# AMP_1_0.net
KiCad netlist of a schematic drawn in EAGLE
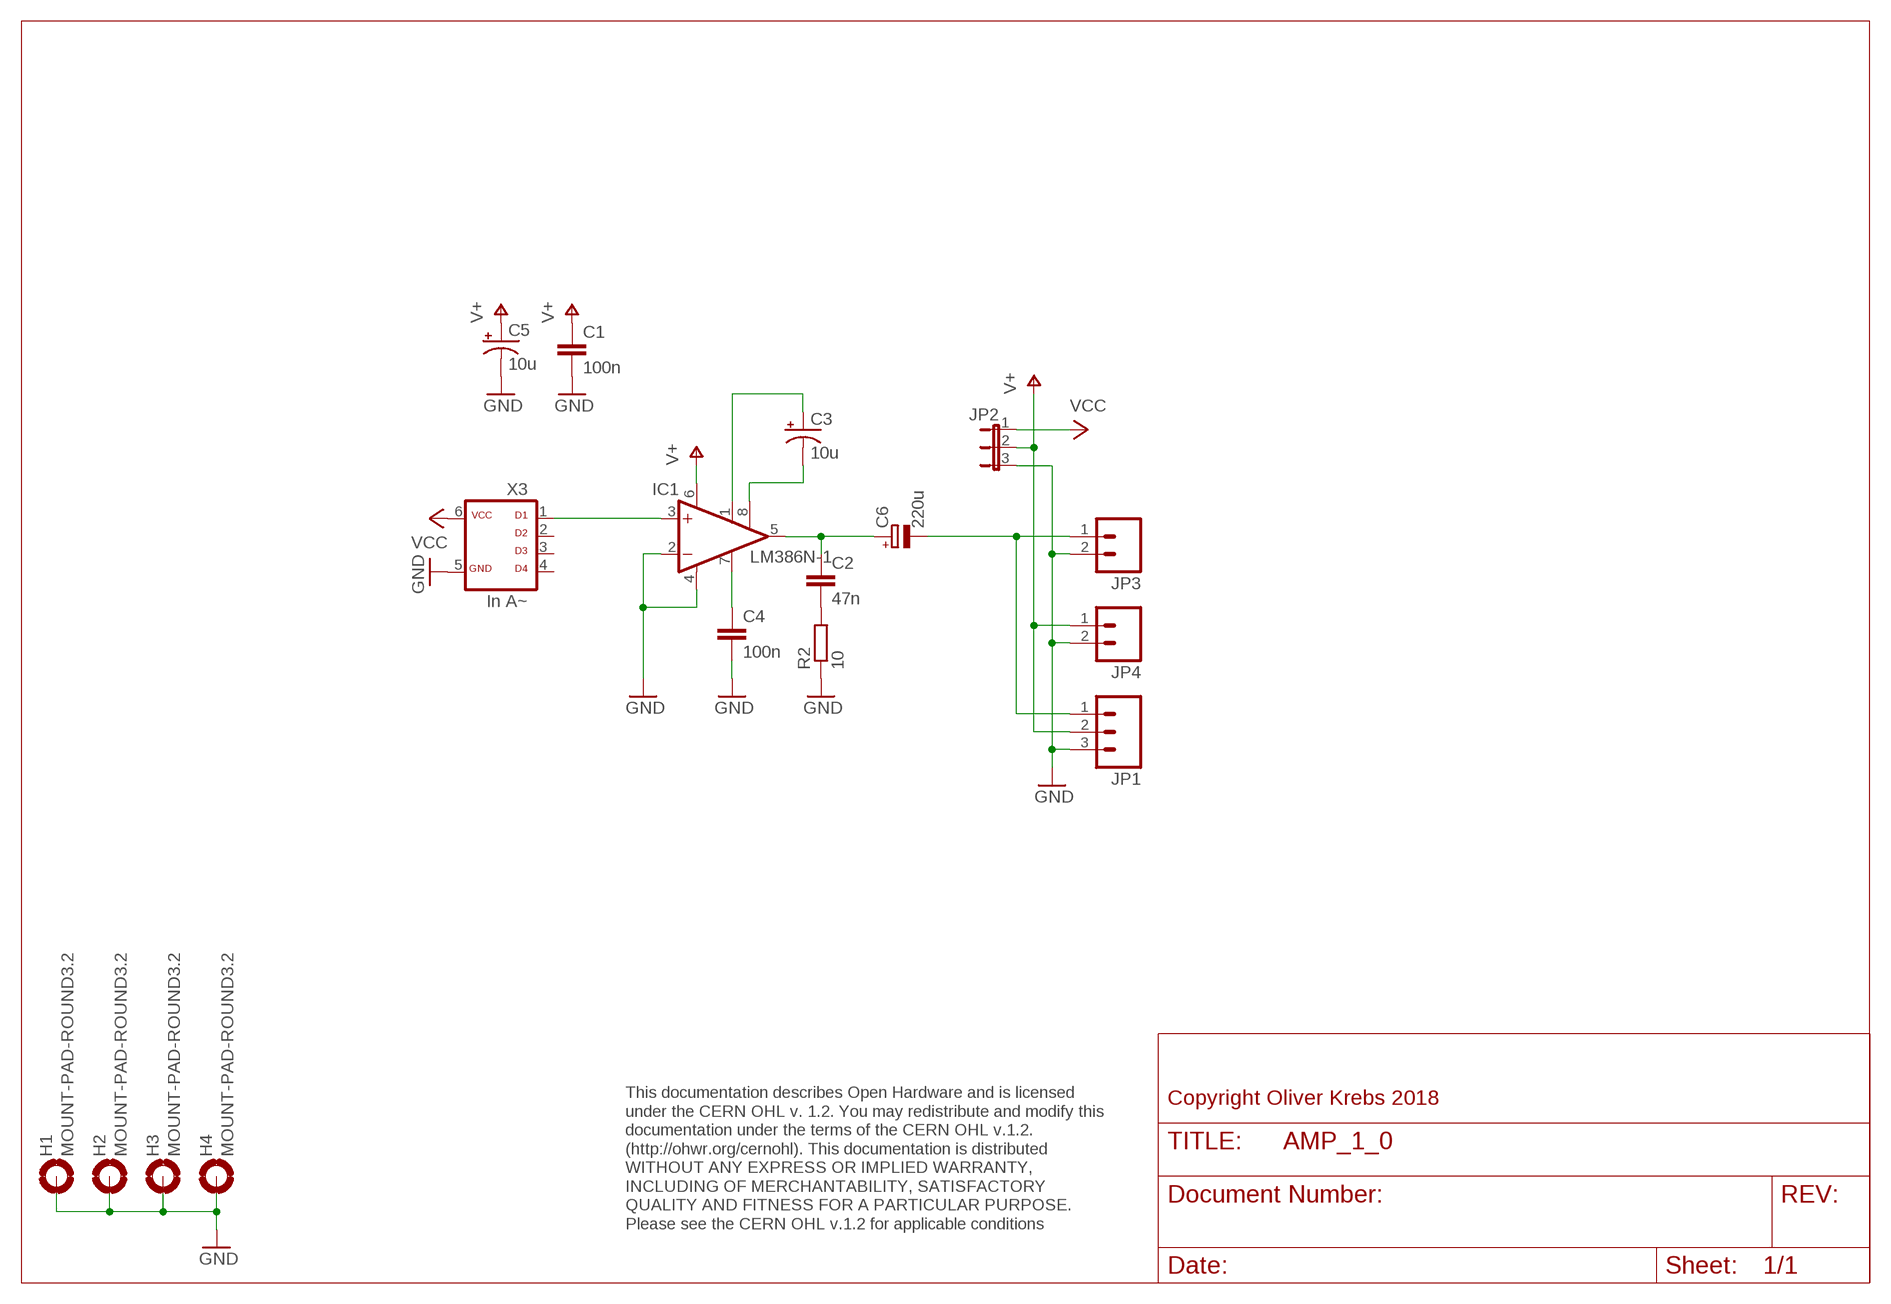
[diagram p0: schematic, sheet 1]

(export (version "E")
  (design (tool "Eeschema 10.0.6"))
  (components
    (comp (ref "C1")
      (value "100n")
      (footprint "eagle-import:C050-025X075")
      (libsource (lib "eagle-import") (part "C-EU050-025X075"))
    )
    (comp (ref "C2")
      (value "47n")
      (footprint "eagle-import:C050-025X075")
      (libsource (lib "eagle-import") (part "C-EU050-025X075"))
    )
    (comp (ref "C3")
      (value "10u")
      (footprint "eagle-import:CPOL-RADIAL-10UF-25V")
      (libsource (lib "eagle-import") (part "CAP_POLPTH2"))
    )
    (comp (ref "C4")
      (value "100n")
      (footprint "eagle-import:C050-025X075")
      (libsource (lib "eagle-import") (part "C-EU050-025X075"))
    )
    (comp (ref "C5")
      (value "10u")
      (footprint "eagle-import:CPOL-RADIAL-10UF-25V")
      (libsource (lib "eagle-import") (part "CAP_POLPTH2"))
    )
    (comp (ref "C6")
      (value "220u")
      (footprint "eagle-import:E3,5-8")
      (libsource (lib "eagle-import") (part "CPOL-EUE3.5-8"))
    )
    (comp (ref "H1")
      (value "MOUNT-PAD-ROUND3.2")
      (footprint "eagle-import:3,2-PAD")
      (libsource (lib "eagle-import") (part "MOUNT-PAD-ROUND3.2"))
    )
    (comp (ref "H2")
      (value "MOUNT-PAD-ROUND3.2")
      (footprint "eagle-import:3,2-PAD")
      (libsource (lib "eagle-import") (part "MOUNT-PAD-ROUND3.2"))
    )
    (comp (ref "H3")
      (value "MOUNT-PAD-ROUND3.2")
      (footprint "eagle-import:3,2-PAD")
      (libsource (lib "eagle-import") (part "MOUNT-PAD-ROUND3.2"))
    )
    (comp (ref "H4")
      (value "MOUNT-PAD-ROUND3.2")
      (footprint "eagle-import:3,2-PAD")
      (libsource (lib "eagle-import") (part "MOUNT-PAD-ROUND3.2"))
    )
    (comp (ref "IC1")
      (value "LM386N-1")
      (footprint "eagle-import:DIL08")
      (libsource (lib "eagle-import") (part "LM386?-N1"))
    )
    (comp (ref "JP1")
      (value "M03PTH")
      (footprint "eagle-import:1X03")
      (libsource (lib "eagle-import") (part "M03PTH"))
    )
    (comp (ref "JP2")
      (value "JP2EJP2-U")
      (footprint "eagle-import:JP2-U")
      (libsource (lib "eagle-import") (part "JP2EJP2-U"))
    )
    (comp (ref "JP3")
      (value "M021.3MM-5.08")
      (footprint "eagle-import:1X02_BIG_5.08")
      (libsource (lib "eagle-import") (part "M021.3MM-5.08"))
    )
    (comp (ref "JP4")
      (value "M021.3MM-5.08")
      (footprint "eagle-import:1X02_BIG_5.08")
      (libsource (lib "eagle-import") (part "M021.3MM-5.08"))
    )
    (comp (ref "R2")
      (value "10")
      (footprint "eagle-import:0207_10")
      (libsource (lib "eagle-import") (part "R-EU_0207/10"))
    )
    (comp (ref "X3")
      (value "In A~")
      (footprint "eagle-import:ML-6")
      (libsource (lib "eagle-import") (part "ML6D"))
    )
  )
  (nets
    (net (code "1") (name "GND") (class "Default")
      (node (ref "C1") (pin "2") (pinfunction "2_2") (pintype "passive"))
      (node (ref "C4") (pin "2") (pinfunction "2_2") (pintype "passive"))
      (node (ref "C5") (pin "2") (pinfunction "-_2") (pintype "passive"))
      (node (ref "H1") (pin "B3,2") (pinfunction "MOUNT_B3,2") (pintype "passive"))
      (node (ref "H2") (pin "B3,2") (pinfunction "MOUNT_B3,2") (pintype "passive"))
      (node (ref "H3") (pin "B3,2") (pinfunction "MOUNT_B3,2") (pintype "passive"))
      (node (ref "H4") (pin "B3,2") (pinfunction "MOUNT_B3,2") (pintype "passive"))
      (node (ref "IC1") (pin "2") (pinfunction "-IN_2") (pintype "input"))
      (node (ref "IC1") (pin "4") (pinfunction "GND_4") (pintype "power_in"))
      (node (ref "JP1") (pin "3") (pinfunction "3_3") (pintype "passive"))
      (node (ref "JP2") (pin "3") (pinfunction "3_3") (pintype "passive"))
      (node (ref "JP3") (pin "2") (pinfunction "2_2") (pintype "passive"))
      (node (ref "JP4") (pin "2") (pinfunction "2_2") (pintype "passive"))
      (node (ref "R2") (pin "1") (pinfunction "1_1") (pintype "passive"))
      (node (ref "X3") (pin "5") (pinfunction "5_5") (pintype "passive"))
    )
    (net (code "2") (name "Net-(C2-Pad2)") (class "Default")
      (node (ref "C2") (pin "2") (pinfunction "2_2") (pintype "passive"))
      (node (ref "R2") (pin "2") (pinfunction "2_2") (pintype "passive"))
    )
    (net (code "3") (name "Net-(C3-+)") (class "Default")
      (node (ref "C3") (pin "1") (pinfunction "+_1") (pintype "passive"))
      (node (ref "IC1") (pin "1") (pinfunction "GAIN_1") (pintype "passive"))
    )
    (net (code "4") (name "Net-(C3--)") (class "Default")
      (node (ref "C3") (pin "2") (pinfunction "-_2") (pintype "passive"))
      (node (ref "IC1") (pin "8") (pinfunction "GAIN_8") (pintype "passive"))
    )
    (net (code "5") (name "Net-(C6-Pad-)") (class "Default")
      (node (ref "C6") (pin "-") (pinfunction "-_-") (pintype "passive"))
      (node (ref "JP1") (pin "1") (pinfunction "1_1") (pintype "passive"))
      (node (ref "JP3") (pin "1") (pinfunction "1_1") (pintype "passive"))
    )
    (net (code "6") (name "Net-(IC1-+IN)") (class "Default")
      (node (ref "IC1") (pin "3") (pinfunction "+IN_3") (pintype "input"))
      (node (ref "X3") (pin "1") (pinfunction "1_1") (pintype "passive"))
    )
    (net (code "7") (name "Net-(IC1-BYPASS)") (class "Default")
      (node (ref "C4") (pin "1") (pinfunction "1_1") (pintype "passive"))
      (node (ref "IC1") (pin "7") (pinfunction "BYPASS_7") (pintype "passive"))
    )
    (net (code "8") (name "Net-(IC1-OUT)") (class "Default")
      (node (ref "C2") (pin "1") (pinfunction "1_1") (pintype "passive"))
      (node (ref "C6") (pin "+") (pinfunction "+_+") (pintype "passive"))
      (node (ref "IC1") (pin "5") (pinfunction "OUT_5") (pintype "output"))
    )
    (net (code "9") (name "V+") (class "Default")
      (node (ref "C1") (pin "1") (pinfunction "1_1") (pintype "passive"))
      (node (ref "C5") (pin "1") (pinfunction "+_1") (pintype "passive"))
      (node (ref "IC1") (pin "6") (pinfunction "VS_6") (pintype "power_in"))
      (node (ref "JP1") (pin "2") (pinfunction "2_2") (pintype "passive"))
      (node (ref "JP2") (pin "2") (pinfunction "2_2") (pintype "passive"))
      (node (ref "JP4") (pin "1") (pinfunction "1_1") (pintype "passive"))
    )
    (net (code "10") (name "VCC") (class "Default")
      (node (ref "JP2") (pin "1") (pinfunction "1_1") (pintype "passive"))
      (node (ref "X3") (pin "6") (pinfunction "6_6") (pintype "passive"))
    )
    (net (code "11") (name "unconnected-(X3-Pad2)") (class "Default")
      (node (ref "X3") (pin "2") (pinfunction "2_2") (pintype "passive"))
    )
    (net (code "12") (name "unconnected-(X3-Pad3)") (class "Default")
      (node (ref "X3") (pin "3") (pinfunction "3_3") (pintype "passive"))
    )
    (net (code "13") (name "unconnected-(X3-Pad4)") (class "Default")
      (node (ref "X3") (pin "4") (pinfunction "4_4") (pintype "passive"))
    )
  )
)
